# Genesis_V1_0.net
KiCad netlist of a schematic drawn in EAGLE
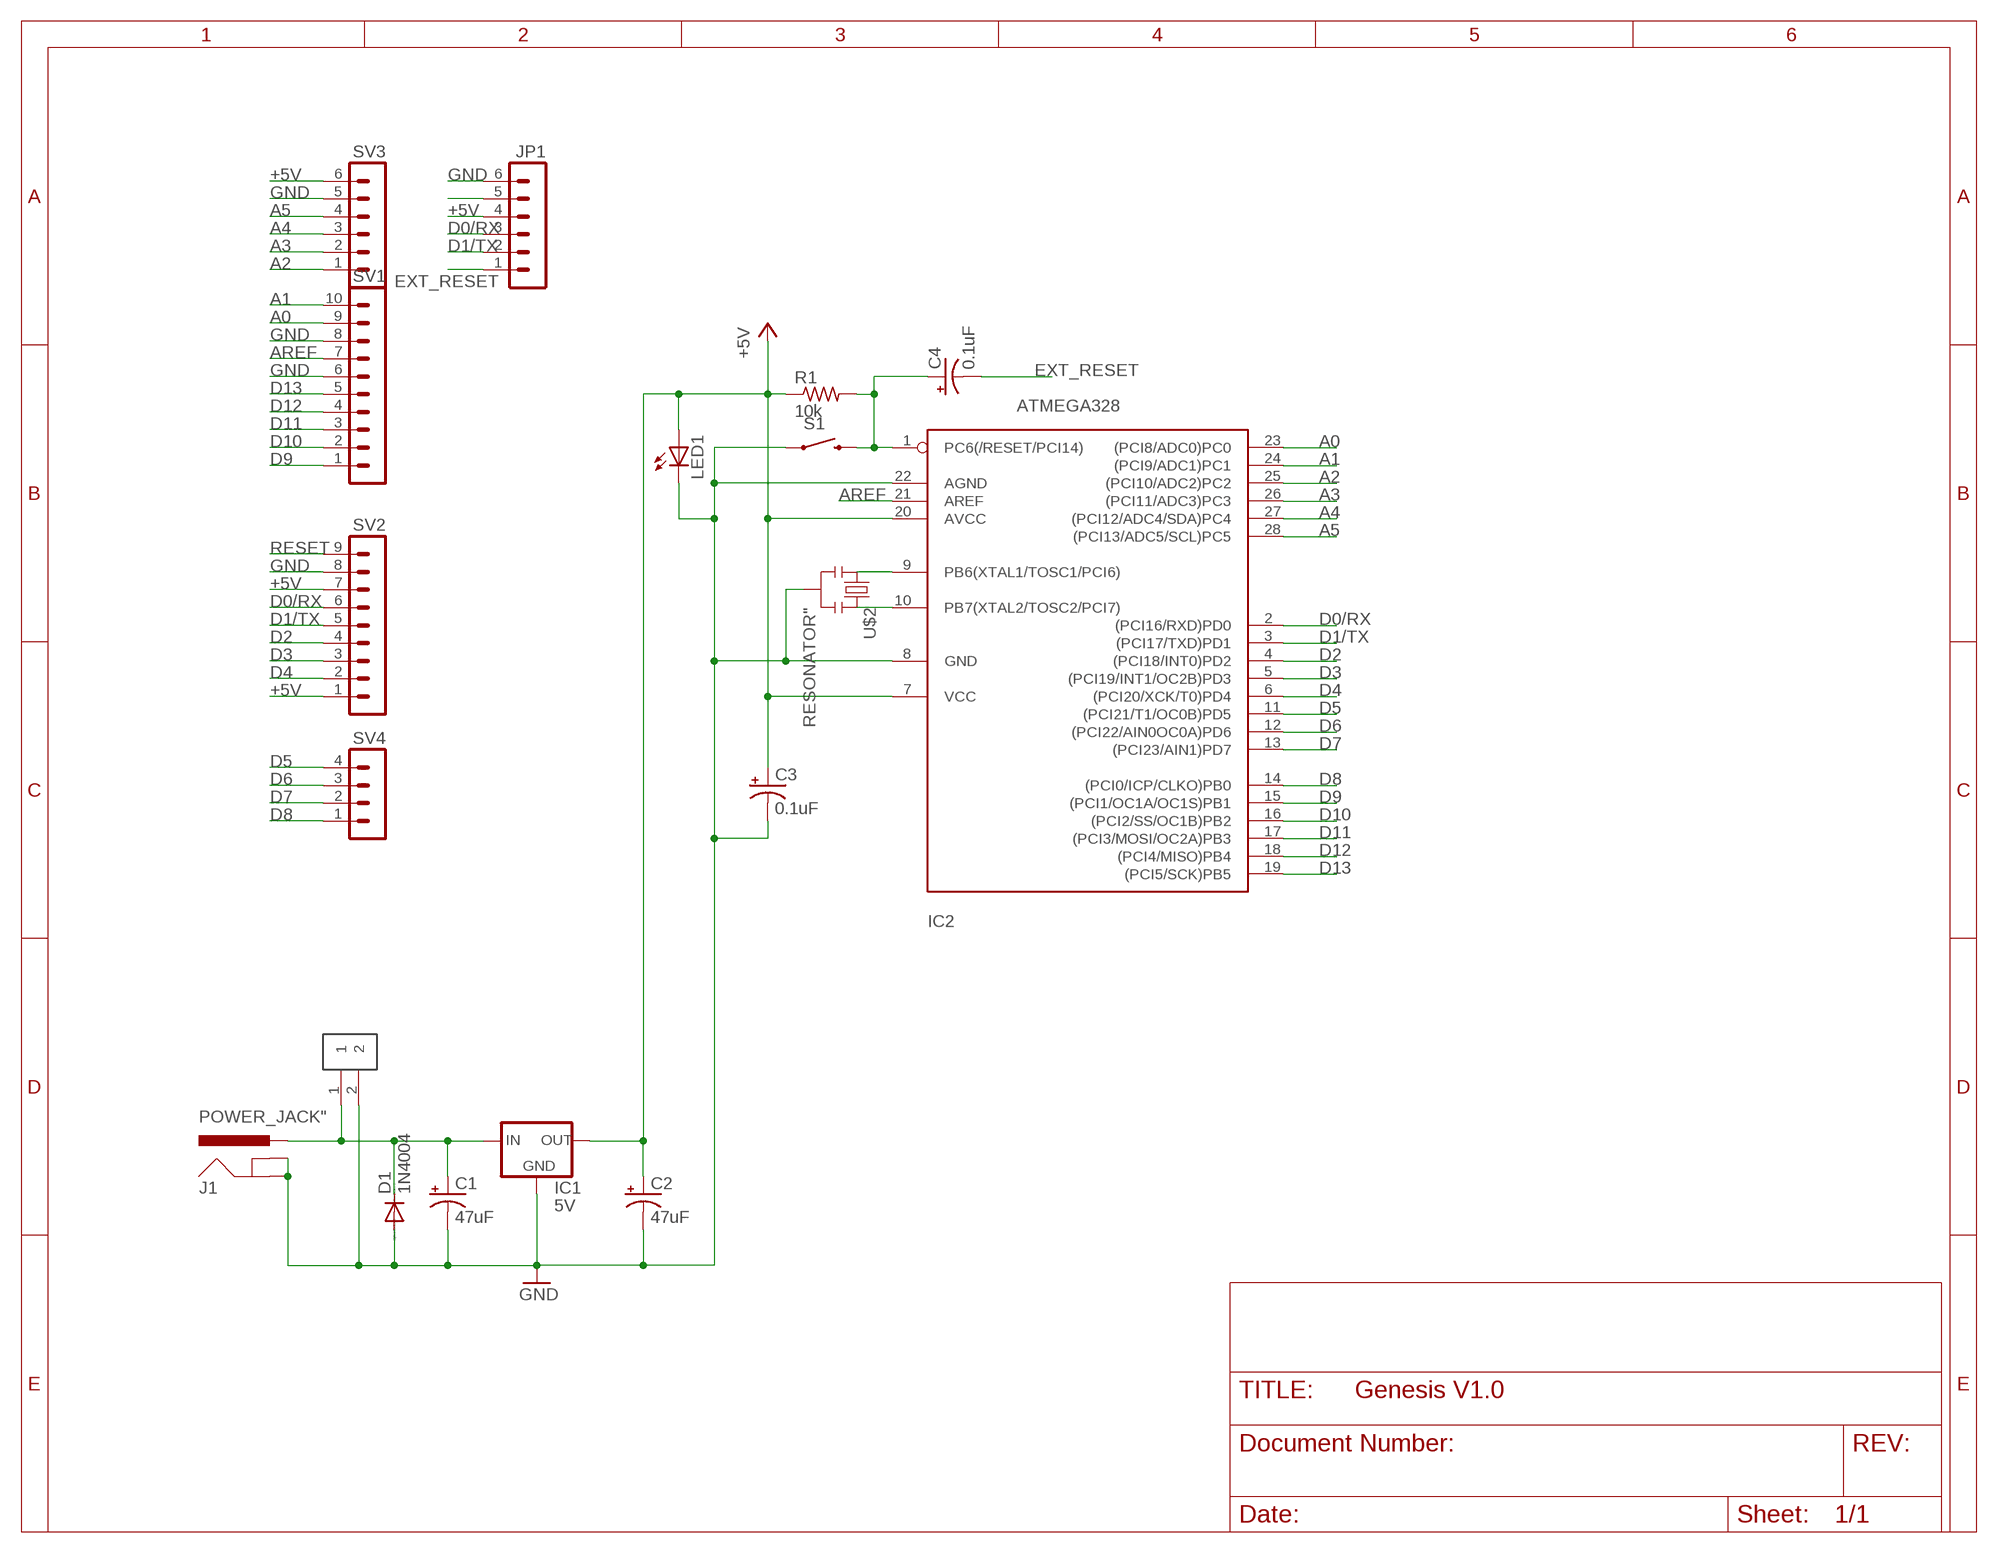
[diagram p0: schematic, sheet 1]

(export (version "E")
  (design (tool "Eeschema 10.0.6"))
  (components
    (comp (ref "C1")
      (value "47uF")
      (footprint "eagle-import:ELECTROLYTIC_CAP")
      (libsource (lib "eagle-import") (part "ELECTROLYTIC_CAP2.54MM"))
    )
    (comp (ref "C2")
      (value "47uF")
      (footprint "eagle-import:ELECTROLYTIC_CAP")
      (libsource (lib "eagle-import") (part "ELECTROLYTIC_CAP2.54MM"))
    )
    (comp (ref "C3")
      (value "0.1uF")
      (footprint "eagle-import:ELECTROLYTIC_CAP")
      (libsource (lib "eagle-import") (part "ELECTROLYTIC_CAP2.54MM"))
    )
    (comp (ref "C4")
      (value "0.1uF")
      (footprint "eagle-import:ELECTROLYTIC_CAP")
      (libsource (lib "eagle-import") (part "ELECTROLYTIC_CAP2.54MM"))
    )
    (comp (ref "D1")
      (value "1N4004")
      (footprint "eagle-import:DO41-10")
      (libsource (lib "eagle-import") (part "1N4004"))
    )
    (comp (ref "IC1")
      (value "5V")
      (footprint "eagle-import:L4931_REGULATOR")
      (libsource (lib "eagle-import") (part "REGULATOR"))
    )
    (comp (ref "IC2")
      (value "ATMEGA328")
      (footprint "eagle-import:ATMEGA328")
      (libsource (lib "eagle-import") (part "ATMEGA328{dblquote}"))
    )
    (comp (ref "J1")
      (value "POWER_JACK\"")
      (footprint "eagle-import:POWER_JACK")
      (libsource (lib "eagle-import") (part "POWER_JACK{dblquote}"))
    )
    (comp (ref "JP1")
      (value "MA06-1")
      (footprint "eagle-import:MA06-1")
      (libsource (lib "eagle-import") (part "MA06-1"))
    )
    (comp (ref "LED1")
      (value "LED3MM")
      (footprint "eagle-import:LED")
      (libsource (lib "eagle-import") (part "LED3MM"))
    )
    (comp (ref "R1")
      (value "10k")
      (footprint "eagle-import:RESISTOR")
      (libsource (lib "eagle-import") (part "RESISTOR1/6WATT"))
    )
    (comp (ref "S1")
      (value "MOMENTARY_SWITCH\"")
      (footprint "eagle-import:MOMENTARY_SWITCH")
      (libsource (lib "eagle-import") (part "MOMENTARY_SWITCH{dblquote}"))
    )
    (comp (ref "SV1")
      (value "MA10-1")
      (footprint "eagle-import:MA10-1")
      (libsource (lib "eagle-import") (part "MA10-1"))
    )
    (comp (ref "SV2")
      (value "MA09-1")
      (footprint "eagle-import:MA09-1")
      (libsource (lib "eagle-import") (part "MA09-1"))
    )
    (comp (ref "SV3")
      (value "MA06-1")
      (footprint "eagle-import:MA06-1")
      (libsource (lib "eagle-import") (part "MA06-1"))
    )
    (comp (ref "SV4")
      (value "MA04-1")
      (footprint "eagle-import:MA04-1")
      (libsource (lib "eagle-import") (part "MA04-1"))
    )
    (comp (ref "U$1")
      (value "1X02_HEADER")
      (footprint "eagle-import:1X02_HEADER")
      (libsource (lib "eagle-import") (part "1X02_HEADER"))
    )
    (comp (ref "U$2")
      (value "RESONATOR\"")
      (footprint "eagle-import:RESONATOR")
      (libsource (lib "eagle-import") (part "RESONATOR{dblquote}"))
    )
  )
  (nets
    (net (code "1") (name "+5V") (class "Default")
      (node (ref "C2") (pin "+") (pinfunction "+_+") (pintype "passive"))
      (node (ref "C3") (pin "+") (pinfunction "+_+") (pintype "passive"))
      (node (ref "IC1") (pin "OUT") (pinfunction "OUT_OUT") (pintype "passive"))
      (node (ref "IC2") (pin "20") (pinfunction "AVCC_20") (pintype "bidirectional"))
      (node (ref "IC2") (pin "7") (pinfunction "VCC_7") (pintype "bidirectional"))
      (node (ref "JP1") (pin "4") (pinfunction "4_4") (pintype "passive"))
      (node (ref "LED1") (pin "A") (pinfunction "A_A") (pintype "passive"))
      (node (ref "R1") (pin "1") (pinfunction "1_1") (pintype "passive"))
      (node (ref "SV2") (pin "1") (pinfunction "1_1") (pintype "passive"))
      (node (ref "SV2") (pin "7") (pinfunction "7_7") (pintype "passive"))
      (node (ref "SV3") (pin "6") (pinfunction "6_6") (pintype "passive"))
    )
    (net (code "2") (name "/A0") (class "Default")
      (node (ref "IC2") (pin "23") (pinfunction "(PCI8/ADC0)PC0_23") (pintype "bidirectional"))
      (node (ref "SV1") (pin "9") (pinfunction "9_9") (pintype "passive"))
    )
    (net (code "3") (name "/A1") (class "Default")
      (node (ref "IC2") (pin "24") (pinfunction "(PCI9/ADC1)PC1_24") (pintype "bidirectional"))
      (node (ref "SV1") (pin "10") (pinfunction "10_10") (pintype "passive"))
    )
    (net (code "4") (name "/A2") (class "Default")
      (node (ref "IC2") (pin "25") (pinfunction "(PCI10/ADC2)PC2_25") (pintype "bidirectional"))
      (node (ref "SV3") (pin "1") (pinfunction "1_1") (pintype "passive"))
    )
    (net (code "5") (name "/A3") (class "Default")
      (node (ref "IC2") (pin "26") (pinfunction "(PCI11/ADC3)PC3_26") (pintype "bidirectional"))
      (node (ref "SV3") (pin "2") (pinfunction "2_2") (pintype "passive"))
    )
    (net (code "6") (name "/A4") (class "Default")
      (node (ref "IC2") (pin "27") (pinfunction "(PCI12/ADC4/SDA)PC4_27") (pintype "bidirectional"))
      (node (ref "SV3") (pin "3") (pinfunction "3_3") (pintype "passive"))
    )
    (net (code "7") (name "/A5") (class "Default")
      (node (ref "IC2") (pin "28") (pinfunction "(PCI13/ADC5/SCL)PC5_28") (pintype "bidirectional"))
      (node (ref "SV3") (pin "4") (pinfunction "4_4") (pintype "passive"))
    )
    (net (code "8") (name "/AREF") (class "Default")
      (node (ref "IC2") (pin "21") (pinfunction "AREF_21") (pintype "bidirectional"))
      (node (ref "SV1") (pin "7") (pinfunction "7_7") (pintype "passive"))
    )
    (net (code "9") (name "/D0{slash}RX") (class "Default")
      (node (ref "IC2") (pin "2") (pinfunction "(PCI16/RXD)PD0_2") (pintype "bidirectional"))
      (node (ref "JP1") (pin "3") (pinfunction "3_3") (pintype "passive"))
      (node (ref "SV2") (pin "6") (pinfunction "6_6") (pintype "passive"))
    )
    (net (code "10") (name "/D1{slash}TX") (class "Default")
      (node (ref "IC2") (pin "3") (pinfunction "(PCI17/TXD)PD1_3") (pintype "bidirectional"))
      (node (ref "JP1") (pin "2") (pinfunction "2_2") (pintype "passive"))
      (node (ref "SV2") (pin "5") (pinfunction "5_5") (pintype "passive"))
    )
    (net (code "11") (name "/D2") (class "Default")
      (node (ref "IC2") (pin "4") (pinfunction "(PCI18/INT0)PD2_4") (pintype "bidirectional"))
      (node (ref "SV2") (pin "4") (pinfunction "4_4") (pintype "passive"))
    )
    (net (code "12") (name "/D3") (class "Default")
      (node (ref "IC2") (pin "5") (pinfunction "(PCI19/INT1/OC2B)PD3_5") (pintype "bidirectional"))
      (node (ref "SV2") (pin "3") (pinfunction "3_3") (pintype "passive"))
    )
    (net (code "13") (name "/D4") (class "Default")
      (node (ref "IC2") (pin "6") (pinfunction "(PCI20/XCK/T0)PD4_6") (pintype "bidirectional"))
      (node (ref "SV2") (pin "2") (pinfunction "2_2") (pintype "passive"))
    )
    (net (code "14") (name "/D5") (class "Default")
      (node (ref "IC2") (pin "11") (pinfunction "(PCI21/T1/OC0B)PD5_11") (pintype "bidirectional"))
      (node (ref "SV4") (pin "4") (pinfunction "4_4") (pintype "passive"))
    )
    (net (code "15") (name "/D6") (class "Default")
      (node (ref "IC2") (pin "12") (pinfunction "(PCI22/AIN0OC0A)PD6_12") (pintype "bidirectional"))
      (node (ref "SV4") (pin "3") (pinfunction "3_3") (pintype "passive"))
    )
    (net (code "16") (name "/D7") (class "Default")
      (node (ref "IC2") (pin "13") (pinfunction "(PCI23/AIN1)PD7_13") (pintype "bidirectional"))
      (node (ref "SV4") (pin "2") (pinfunction "2_2") (pintype "passive"))
    )
    (net (code "17") (name "/D8") (class "Default")
      (node (ref "IC2") (pin "14") (pinfunction "(PCI0/ICP/CLKO)PB0_14") (pintype "bidirectional"))
      (node (ref "SV4") (pin "1") (pinfunction "1_1") (pintype "passive"))
    )
    (net (code "18") (name "/D9") (class "Default")
      (node (ref "IC2") (pin "15") (pinfunction "(PCI1/OC1A/OC1S)PB1_15") (pintype "bidirectional"))
      (node (ref "SV1") (pin "1") (pinfunction "1_1") (pintype "passive"))
    )
    (net (code "19") (name "/D10") (class "Default")
      (node (ref "IC2") (pin "16") (pinfunction "(PCI2/SS/OC1B)PB2_16") (pintype "bidirectional"))
      (node (ref "SV1") (pin "2") (pinfunction "2_2") (pintype "passive"))
    )
    (net (code "20") (name "/D11") (class "Default")
      (node (ref "IC2") (pin "17") (pinfunction "(PCI3/MOSI/OC2A)PB3_17") (pintype "bidirectional"))
      (node (ref "SV1") (pin "3") (pinfunction "3_3") (pintype "passive"))
    )
    (net (code "21") (name "/D12") (class "Default")
      (node (ref "IC2") (pin "18") (pinfunction "(PCI4/MISO)PB4_18") (pintype "bidirectional"))
      (node (ref "SV1") (pin "4") (pinfunction "4_4") (pintype "passive"))
    )
    (net (code "22") (name "/D13") (class "Default")
      (node (ref "IC2") (pin "19") (pinfunction "(PCI5/SCK)PB5_19") (pintype "bidirectional"))
      (node (ref "SV1") (pin "5") (pinfunction "5_5") (pintype "passive"))
    )
    (net (code "23") (name "/EXT_RESET") (class "Default")
      (node (ref "C4") (pin "-") (pinfunction "-_-") (pintype "passive"))
      (node (ref "JP1") (pin "1") (pinfunction "1_1") (pintype "passive"))
    )
    (net (code "24") (name "/RESET") (class "Default")
      (node (ref "C4") (pin "+") (pinfunction "+_+") (pintype "passive"))
      (node (ref "IC2") (pin "1") (pinfunction "PC6(/RESET/PCI14)_1") (pintype "bidirectional"))
      (node (ref "R1") (pin "2") (pinfunction "2_2") (pintype "passive"))
      (node (ref "S1") (pin "3") (pinfunction "2_3") (pintype "passive"))
      (node (ref "SV2") (pin "9") (pinfunction "9_9") (pintype "passive"))
    )
    (net (code "25") (name "GND") (class "Default")
      (node (ref "C1") (pin "-") (pinfunction "-_-") (pintype "passive"))
      (node (ref "C2") (pin "-") (pinfunction "-_-") (pintype "passive"))
      (node (ref "C3") (pin "-") (pinfunction "-_-") (pintype "passive"))
      (node (ref "D1") (pin "A") (pinfunction "A_A") (pintype "passive"))
      (node (ref "IC1") (pin "GND") (pinfunction "GND_GND") (pintype "input"))
      (node (ref "IC2") (pin "22") (pinfunction "AGND_22") (pintype "bidirectional"))
      (node (ref "IC2") (pin "8") (pinfunction "GND_8") (pintype "bidirectional"))
      (node (ref "J1") (pin "GND") (pinfunction "GND_GND") (pintype "bidirectional"))
      (node (ref "J1") (pin "GNDBREAK") (pinfunction "GNDBREAK_GNDBREAK") (pintype "bidirectional"))
      (node (ref "JP1") (pin "6") (pinfunction "6_6") (pintype "passive"))
      (node (ref "LED1") (pin "K") (pinfunction "C_K") (pintype "passive"))
      (node (ref "S1") (pin "1") (pinfunction "1_1") (pintype "passive"))
      (node (ref "SV1") (pin "6") (pinfunction "6_6") (pintype "passive"))
      (node (ref "SV1") (pin "8") (pinfunction "8_8") (pintype "passive"))
      (node (ref "SV2") (pin "8") (pinfunction "8_8") (pintype "passive"))
      (node (ref "SV3") (pin "5") (pinfunction "5_5") (pintype "passive"))
      (node (ref "U$1") (pin "2") (pinfunction "2_2") (pintype "bidirectional"))
      (node (ref "U$2") (pin "2") (pinfunction "2_2") (pintype "passive"))
    )
    (net (code "26") (name "Net-(C1-Pad+)") (class "Default")
      (node (ref "C1") (pin "+") (pinfunction "+_+") (pintype "passive"))
      (node (ref "D1") (pin "C") (pinfunction "C_C") (pintype "passive"))
      (node (ref "IC1") (pin "IN") (pinfunction "IN_IN") (pintype "input"))
      (node (ref "J1") (pin "PWR") (pinfunction "PWR_PWR") (pintype "bidirectional"))
      (node (ref "U$1") (pin "1") (pinfunction "1_1") (pintype "bidirectional"))
    )
    (net (code "27") (name "Net-(IC2-PB6(XTAL1{slash}TOSC1{slash}PCI6))") (class "Default")
      (node (ref "IC2") (pin "9") (pinfunction "PB6(XTAL1/TOSC1/PCI6)_9") (pintype "bidirectional"))
      (node (ref "U$2") (pin "1") (pinfunction "1_1") (pintype "passive"))
    )
    (net (code "28") (name "Net-(IC2-PB7(XTAL2{slash}TOSC2{slash}PCI7))") (class "Default")
      (node (ref "IC2") (pin "10") (pinfunction "PB7(XTAL2/TOSC2/PCI7)_10") (pintype "bidirectional"))
      (node (ref "U$2") (pin "3") (pinfunction "3_3") (pintype "passive"))
    )
    (net (code "29") (name "unconnected-(JP1-Pad5)") (class "Default")
      (node (ref "JP1") (pin "5") (pinfunction "5_5") (pintype "passive"))
    )
  )
)
